# LaunchPadSpiBus2.net
KiCad netlist of a schematic drawn in EAGLE
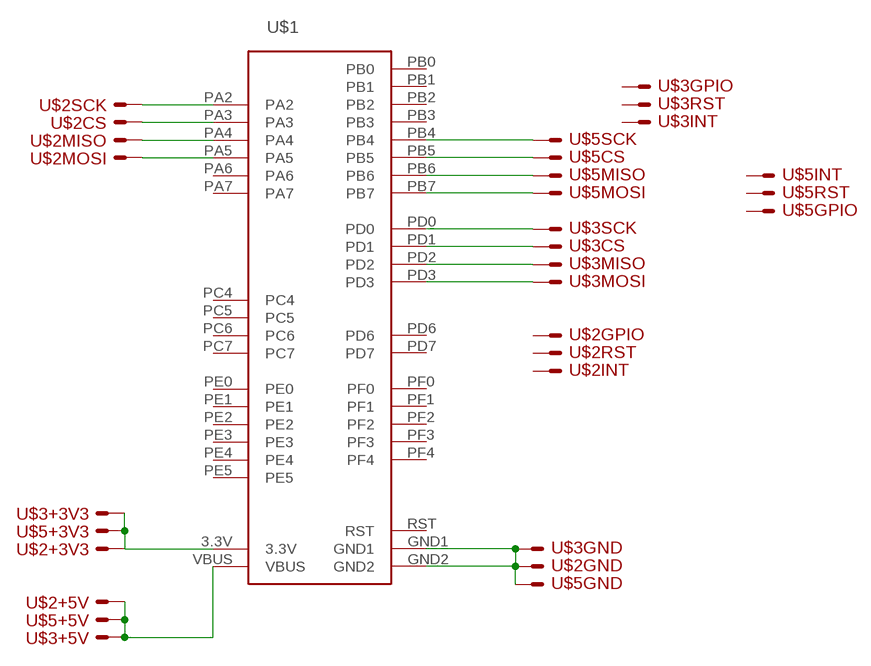
[diagram p0: schematic, sheet 1]

(export (version "E")
  (design (tool "Eeschema 10.0.6"))
  (components
    (comp (ref "U$1")
      (value "STELLARIS-LAUNCHPADSTELLARIS-LAUNCHPAD-XL")
      (footprint "eagle-import:LAUNCHPAD-XL")
      (libsource (lib "eagle-import") (part "STELLARIS-LAUNCHPADSTELLARIS-LAUNCHPAD-XL"))
    )
    (comp (ref "U$2")
      (value "SPI_BUS")
      (footprint "eagle-import:SPI_BUS")
      (libsource (lib "eagle-import") (part "SPI_BUS"))
    )
    (comp (ref "U$3")
      (value "SPI_BUS")
      (footprint "eagle-import:SPI_BUS")
      (libsource (lib "eagle-import") (part "SPI_BUS"))
    )
    (comp (ref "U$5")
      (value "SPI_BUS")
      (footprint "eagle-import:SPI_BUS")
      (libsource (lib "eagle-import") (part "SPI_BUS"))
    )
  )
  (nets
    (net (code "1") (name "/RST") (class "Default")
      (node (ref "U$1") (pin "RST") (pinfunction "RST_RST") (pintype "power_in"))
    )
    (net (code "2") (name "Net-(U$2A-S)") (class "Default")
      (node (ref "U$1") (pin "3.3V") (pinfunction "3.3V_3.3V") (pintype "power_in"))
      (node (ref "U$2") (pin "+3V3") (pinfunction "S_+3V3") (pintype "passive"))
      (node (ref "U$3") (pin "+3V3") (pinfunction "S_+3V3") (pintype "passive"))
      (node (ref "U$5") (pin "+3V3") (pinfunction "S_+3V3") (pintype "passive"))
    )
    (net (code "3") (name "Net-(U$2B-S)") (class "Default")
      (node (ref "U$1") (pin "VBUS") (pinfunction "VBUS_VBUS") (pintype "power_in"))
      (node (ref "U$2") (pin "+5V") (pinfunction "S_+5V") (pintype "passive"))
      (node (ref "U$3") (pin "+5V") (pinfunction "S_+5V") (pintype "passive"))
      (node (ref "U$5") (pin "+5V") (pinfunction "S_+5V") (pintype "passive"))
    )
    (net (code "4") (name "Net-(U$2C-S)") (class "Default")
      (node (ref "U$1") (pin "PA3") (pinfunction "PA3_PA3") (pintype "bidirectional"))
      (node (ref "U$2") (pin "CS") (pinfunction "S_CS") (pintype "passive"))
    )
    (net (code "5") (name "Net-(U$2D-S)") (class "Default")
      (node (ref "U$1") (pin "GND1") (pinfunction "GND1_GND1") (pintype "bidirectional"))
      (node (ref "U$1") (pin "GND2") (pinfunction "GND2_GND2") (pintype "power_in"))
      (node (ref "U$2") (pin "GND") (pinfunction "S_GND") (pintype "passive"))
      (node (ref "U$3") (pin "GND") (pinfunction "S_GND") (pintype "passive"))
      (node (ref "U$5") (pin "GND") (pinfunction "S_GND") (pintype "passive"))
    )
    (net (code "6") (name "Net-(U$2G-S)") (class "Default")
      (node (ref "U$1") (pin "PA4") (pinfunction "PA4_PA4") (pintype "bidirectional"))
      (node (ref "U$2") (pin "MISO") (pinfunction "S_MISO") (pintype "passive"))
    )
    (net (code "7") (name "Net-(U$2H-S)") (class "Default")
      (node (ref "U$1") (pin "PA5") (pinfunction "PA5_PA5") (pintype "bidirectional"))
      (node (ref "U$2") (pin "MOSI") (pinfunction "S_MOSI") (pintype "passive"))
    )
    (net (code "8") (name "Net-(U$2J-S)") (class "Default")
      (node (ref "U$1") (pin "PA2") (pinfunction "PA2_PA2") (pintype "bidirectional"))
      (node (ref "U$2") (pin "SCK") (pinfunction "S_SCK") (pintype "passive"))
    )
    (net (code "9") (name "Net-(U$3C-S)") (class "Default")
      (node (ref "U$1") (pin "PD1") (pinfunction "PD1_PD1") (pintype "bidirectional"))
      (node (ref "U$3") (pin "CS") (pinfunction "S_CS") (pintype "passive"))
    )
    (net (code "10") (name "Net-(U$3G-S)") (class "Default")
      (node (ref "U$1") (pin "PD2") (pinfunction "PD2_PD2") (pintype "bidirectional"))
      (node (ref "U$3") (pin "MISO") (pinfunction "S_MISO") (pintype "passive"))
    )
    (net (code "11") (name "Net-(U$3H-S)") (class "Default")
      (node (ref "U$1") (pin "PD3") (pinfunction "PD3_PD3") (pintype "bidirectional"))
      (node (ref "U$3") (pin "MOSI") (pinfunction "S_MOSI") (pintype "passive"))
    )
    (net (code "12") (name "Net-(U$3J-S)") (class "Default")
      (node (ref "U$1") (pin "PD0") (pinfunction "PD0_PD0") (pintype "bidirectional"))
      (node (ref "U$3") (pin "SCK") (pinfunction "S_SCK") (pintype "passive"))
    )
    (net (code "13") (name "Net-(U$5C-S)") (class "Default")
      (node (ref "U$1") (pin "PB5") (pinfunction "PB5_PB5") (pintype "bidirectional"))
      (node (ref "U$5") (pin "CS") (pinfunction "S_CS") (pintype "passive"))
    )
    (net (code "14") (name "Net-(U$5G-S)") (class "Default")
      (node (ref "U$1") (pin "PB6") (pinfunction "PB6_PB6") (pintype "bidirectional"))
      (node (ref "U$5") (pin "MISO") (pinfunction "S_MISO") (pintype "passive"))
    )
    (net (code "15") (name "Net-(U$5H-S)") (class "Default")
      (node (ref "U$1") (pin "PB7") (pinfunction "PB7_PB7") (pintype "bidirectional"))
      (node (ref "U$5") (pin "MOSI") (pinfunction "S_MOSI") (pintype "passive"))
    )
    (net (code "16") (name "Net-(U$5J-S)") (class "Default")
      (node (ref "U$1") (pin "PB4") (pinfunction "PB4_PB4") (pintype "bidirectional"))
      (node (ref "U$5") (pin "SCK") (pinfunction "S_SCK") (pintype "passive"))
    )
    (net (code "17") (name "unconnected-(U$1-PadPA6)") (class "Default")
      (node (ref "U$1") (pin "PA6") (pinfunction "PA6_PA6") (pintype "bidirectional"))
    )
    (net (code "18") (name "unconnected-(U$1-PadPA7)") (class "Default")
      (node (ref "U$1") (pin "PA7") (pinfunction "PA7_PA7") (pintype "bidirectional"))
    )
    (net (code "19") (name "unconnected-(U$1-PadPB0)") (class "Default")
      (node (ref "U$1") (pin "PB0") (pinfunction "PB0_PB0") (pintype "bidirectional"))
    )
    (net (code "20") (name "unconnected-(U$1-PadPB1)") (class "Default")
      (node (ref "U$1") (pin "PB1") (pinfunction "PB1_PB1") (pintype "bidirectional"))
    )
    (net (code "21") (name "unconnected-(U$1-PadPB2)") (class "Default")
      (node (ref "U$1") (pin "PB2") (pinfunction "PB2_PB2") (pintype "bidirectional"))
    )
    (net (code "22") (name "unconnected-(U$1-PadPB3)") (class "Default")
      (node (ref "U$1") (pin "PB3") (pinfunction "PB3_PB3") (pintype "bidirectional"))
    )
    (net (code "23") (name "unconnected-(U$1-PadPC4)") (class "Default")
      (node (ref "U$1") (pin "PC4") (pinfunction "PC4_PC4") (pintype "bidirectional"))
    )
    (net (code "24") (name "unconnected-(U$1-PadPC5)") (class "Default")
      (node (ref "U$1") (pin "PC5") (pinfunction "PC5_PC5") (pintype "bidirectional"))
    )
    (net (code "25") (name "unconnected-(U$1-PadPC6)") (class "Default")
      (node (ref "U$1") (pin "PC6") (pinfunction "PC6_PC6") (pintype "bidirectional"))
    )
    (net (code "26") (name "unconnected-(U$1-PadPC7)") (class "Default")
      (node (ref "U$1") (pin "PC7") (pinfunction "PC7_PC7") (pintype "bidirectional"))
    )
    (net (code "27") (name "unconnected-(U$1-PadPD6)") (class "Default")
      (node (ref "U$1") (pin "PD6") (pinfunction "PD6_PD6") (pintype "bidirectional"))
    )
    (net (code "28") (name "unconnected-(U$1-PadPD7)") (class "Default")
      (node (ref "U$1") (pin "PD7") (pinfunction "PD7_PD7") (pintype "bidirectional"))
    )
    (net (code "29") (name "unconnected-(U$1-PadPE0)") (class "Default")
      (node (ref "U$1") (pin "PE0") (pinfunction "PE0_PE0") (pintype "bidirectional"))
    )
    (net (code "30") (name "unconnected-(U$1-PadPE1)") (class "Default")
      (node (ref "U$1") (pin "PE1") (pinfunction "PE1_PE1") (pintype "bidirectional"))
    )
    (net (code "31") (name "unconnected-(U$1-PadPE2)") (class "Default")
      (node (ref "U$1") (pin "PE2") (pinfunction "PE2_PE2") (pintype "bidirectional"))
    )
    (net (code "32") (name "unconnected-(U$1-PadPE3)") (class "Default")
      (node (ref "U$1") (pin "PE3") (pinfunction "PE3_PE3") (pintype "bidirectional"))
    )
    (net (code "33") (name "unconnected-(U$1-PadPE4)") (class "Default")
      (node (ref "U$1") (pin "PE4") (pinfunction "PE4_PE4") (pintype "bidirectional"))
    )
    (net (code "34") (name "unconnected-(U$1-PadPE5)") (class "Default")
      (node (ref "U$1") (pin "PE5") (pinfunction "PE5_PE5") (pintype "bidirectional"))
    )
    (net (code "35") (name "unconnected-(U$1-PadPF0)") (class "Default")
      (node (ref "U$1") (pin "PF0") (pinfunction "PF0_PF0") (pintype "bidirectional"))
    )
    (net (code "36") (name "unconnected-(U$1-PadPF1)") (class "Default")
      (node (ref "U$1") (pin "PF1") (pinfunction "PF1_PF1") (pintype "bidirectional"))
    )
    (net (code "37") (name "unconnected-(U$1-PadPF2)") (class "Default")
      (node (ref "U$1") (pin "PF2") (pinfunction "PF2_PF2") (pintype "bidirectional"))
    )
    (net (code "38") (name "unconnected-(U$1-PadPF3)") (class "Default")
      (node (ref "U$1") (pin "PF3") (pinfunction "PF3_PF3") (pintype "bidirectional"))
    )
    (net (code "39") (name "unconnected-(U$1-PadPF4)") (class "Default")
      (node (ref "U$1") (pin "PF4") (pinfunction "PF4_PF4") (pintype "bidirectional"))
    )
    (net (code "40") (name "unconnected-(U$2E-S-PadGPIO)") (class "Default")
      (node (ref "U$2") (pin "GPIO") (pinfunction "S_GPIO") (pintype "passive"))
    )
    (net (code "41") (name "unconnected-(U$2F-S-PadINT)") (class "Default")
      (node (ref "U$2") (pin "INT") (pinfunction "S_INT") (pintype "passive"))
    )
    (net (code "42") (name "unconnected-(U$2I-S-PadRST)") (class "Default")
      (node (ref "U$2") (pin "RST") (pinfunction "S_RST") (pintype "passive"))
    )
    (net (code "43") (name "unconnected-(U$3E-S-PadGPIO)") (class "Default")
      (node (ref "U$3") (pin "GPIO") (pinfunction "S_GPIO") (pintype "passive"))
    )
    (net (code "44") (name "unconnected-(U$3F-S-PadINT)") (class "Default")
      (node (ref "U$3") (pin "INT") (pinfunction "S_INT") (pintype "passive"))
    )
    (net (code "45") (name "unconnected-(U$3I-S-PadRST)") (class "Default")
      (node (ref "U$3") (pin "RST") (pinfunction "S_RST") (pintype "passive"))
    )
    (net (code "46") (name "unconnected-(U$5E-S-PadGPIO)") (class "Default")
      (node (ref "U$5") (pin "GPIO") (pinfunction "S_GPIO") (pintype "passive"))
    )
    (net (code "47") (name "unconnected-(U$5F-S-PadINT)") (class "Default")
      (node (ref "U$5") (pin "INT") (pinfunction "S_INT") (pintype "passive"))
    )
    (net (code "48") (name "unconnected-(U$5I-S-PadRST)") (class "Default")
      (node (ref "U$5") (pin "RST") (pinfunction "S_RST") (pintype "passive"))
    )
  )
)
